# WG-DH-MB.net
KiCad netlist of a schematic drawn in Altium Designer
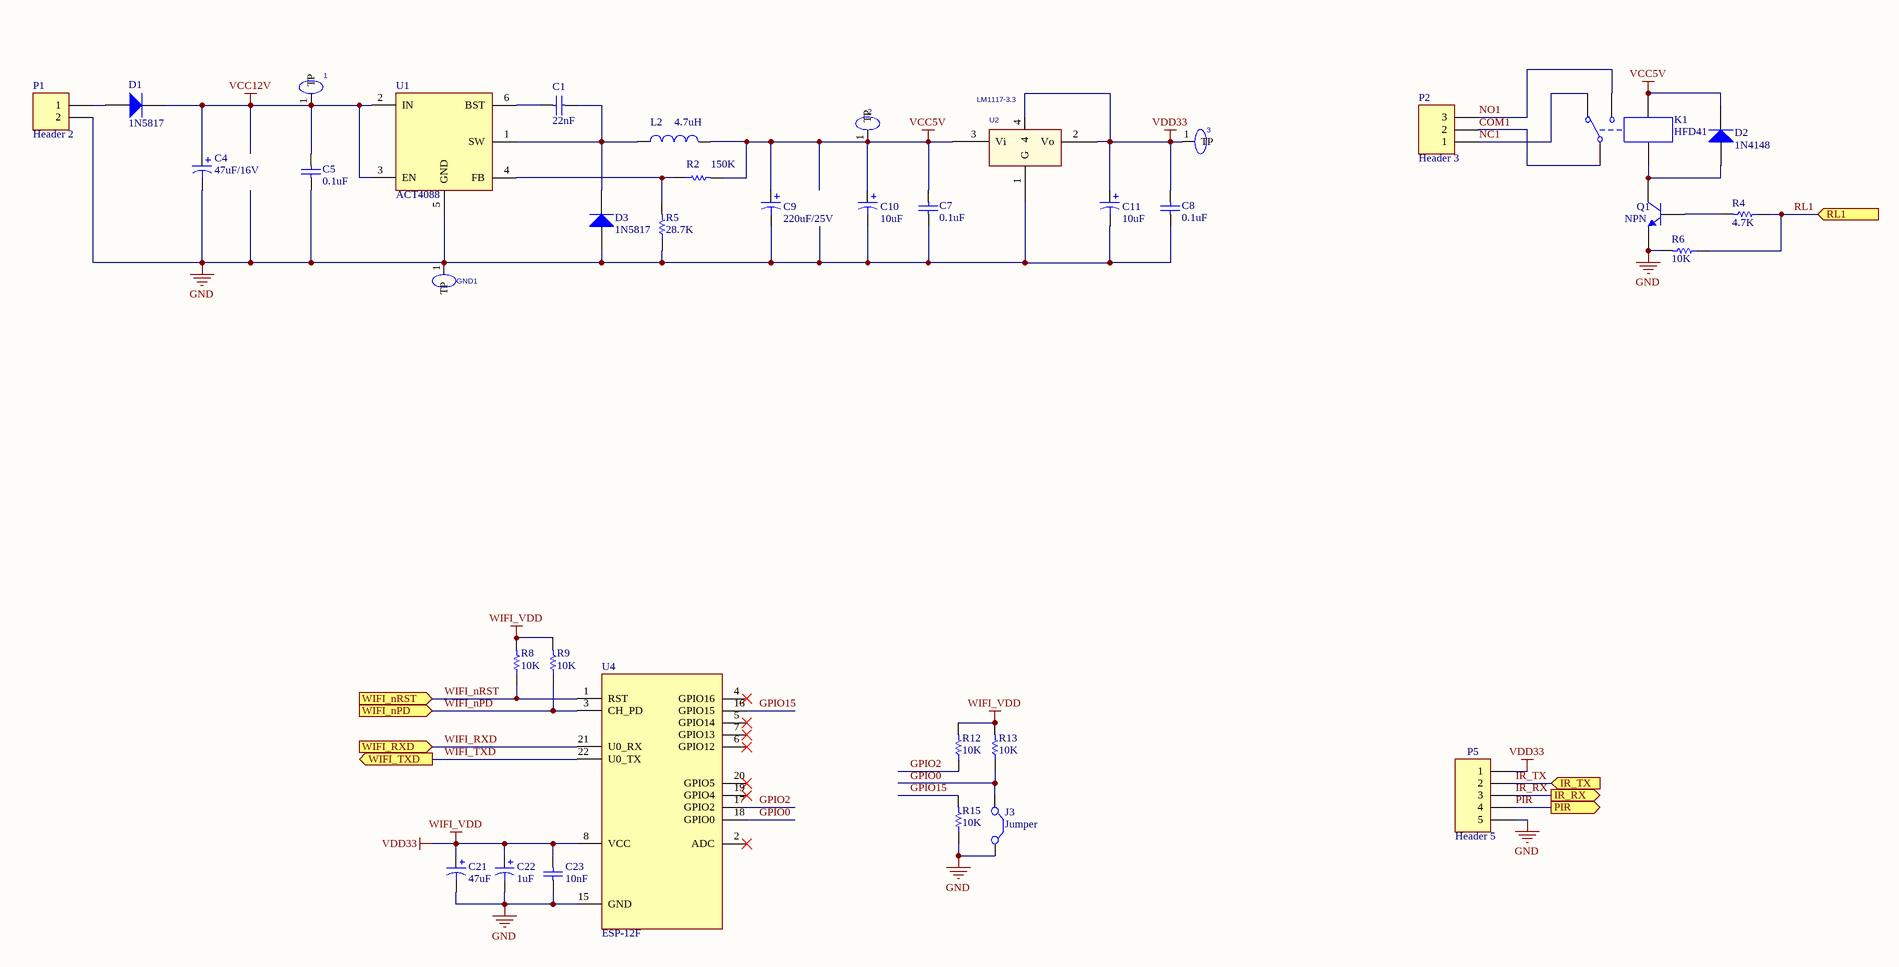
[diagram p0: WG-DH-MB.SchDoc, top left]
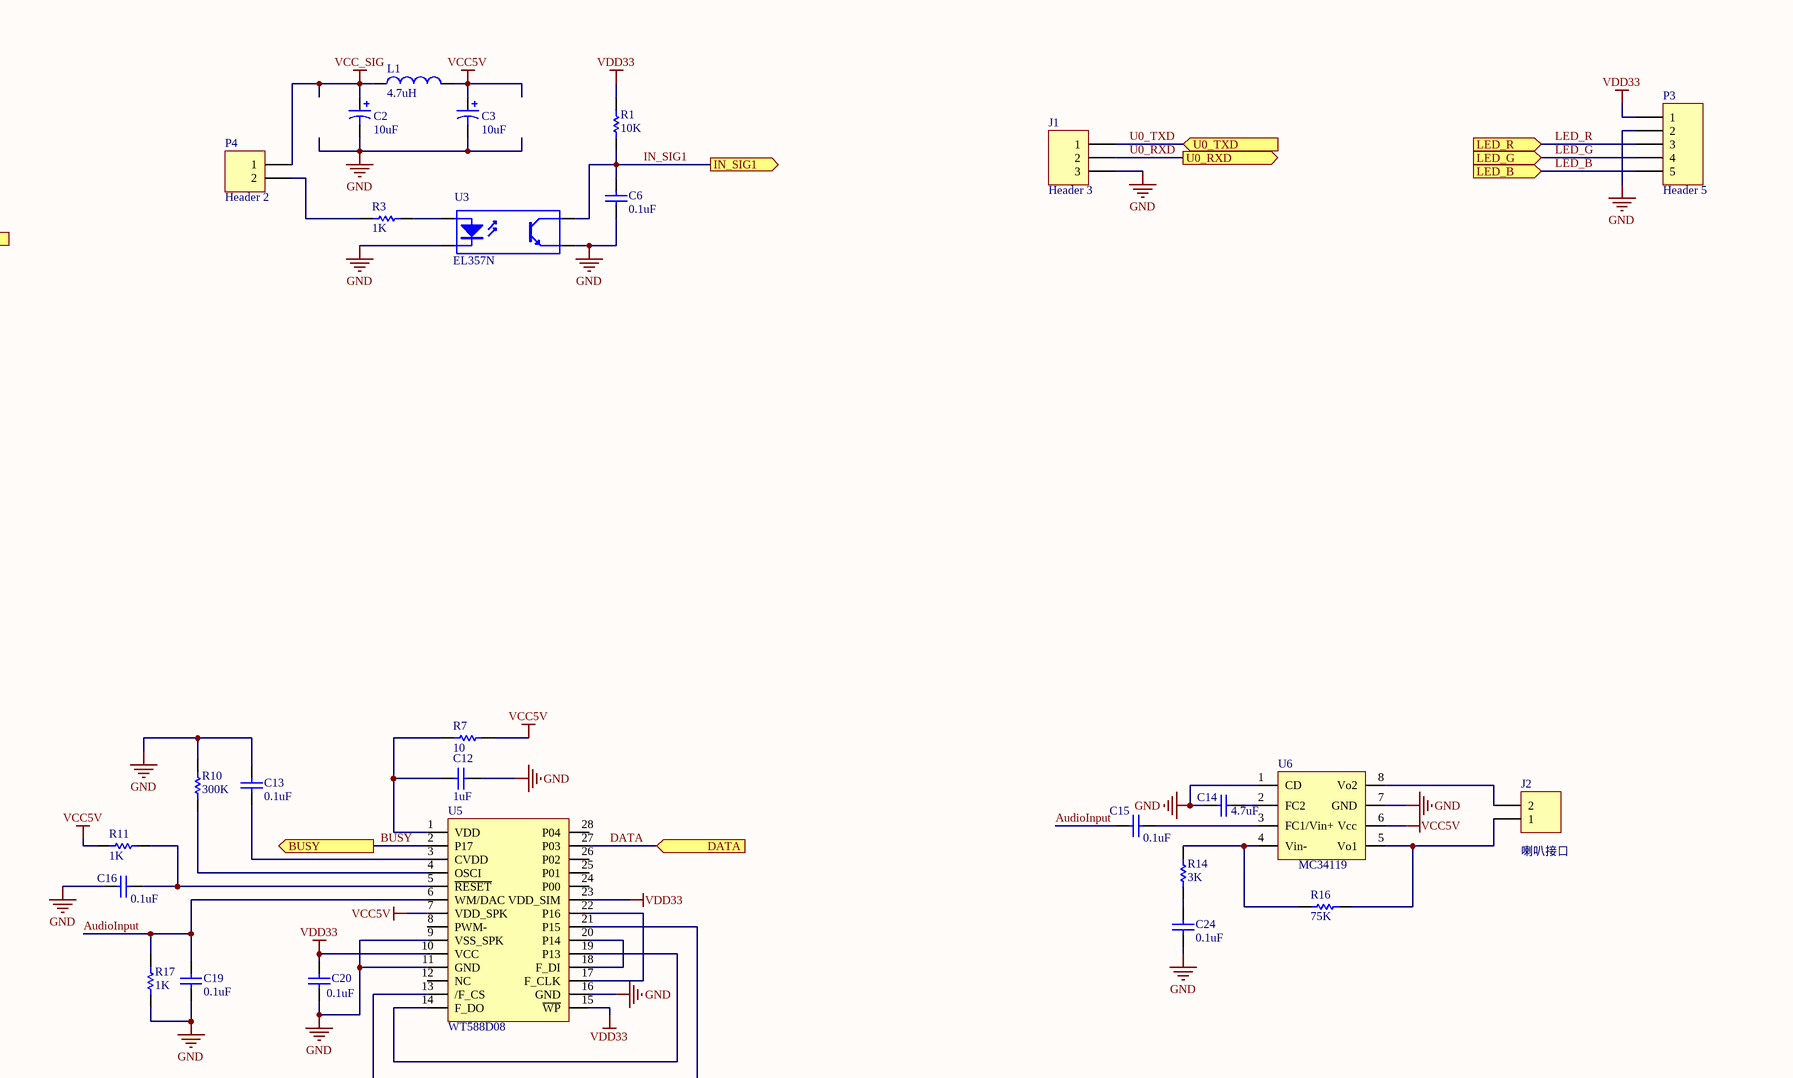
[diagram p1: WG-DH-MB.SchDoc, top right]
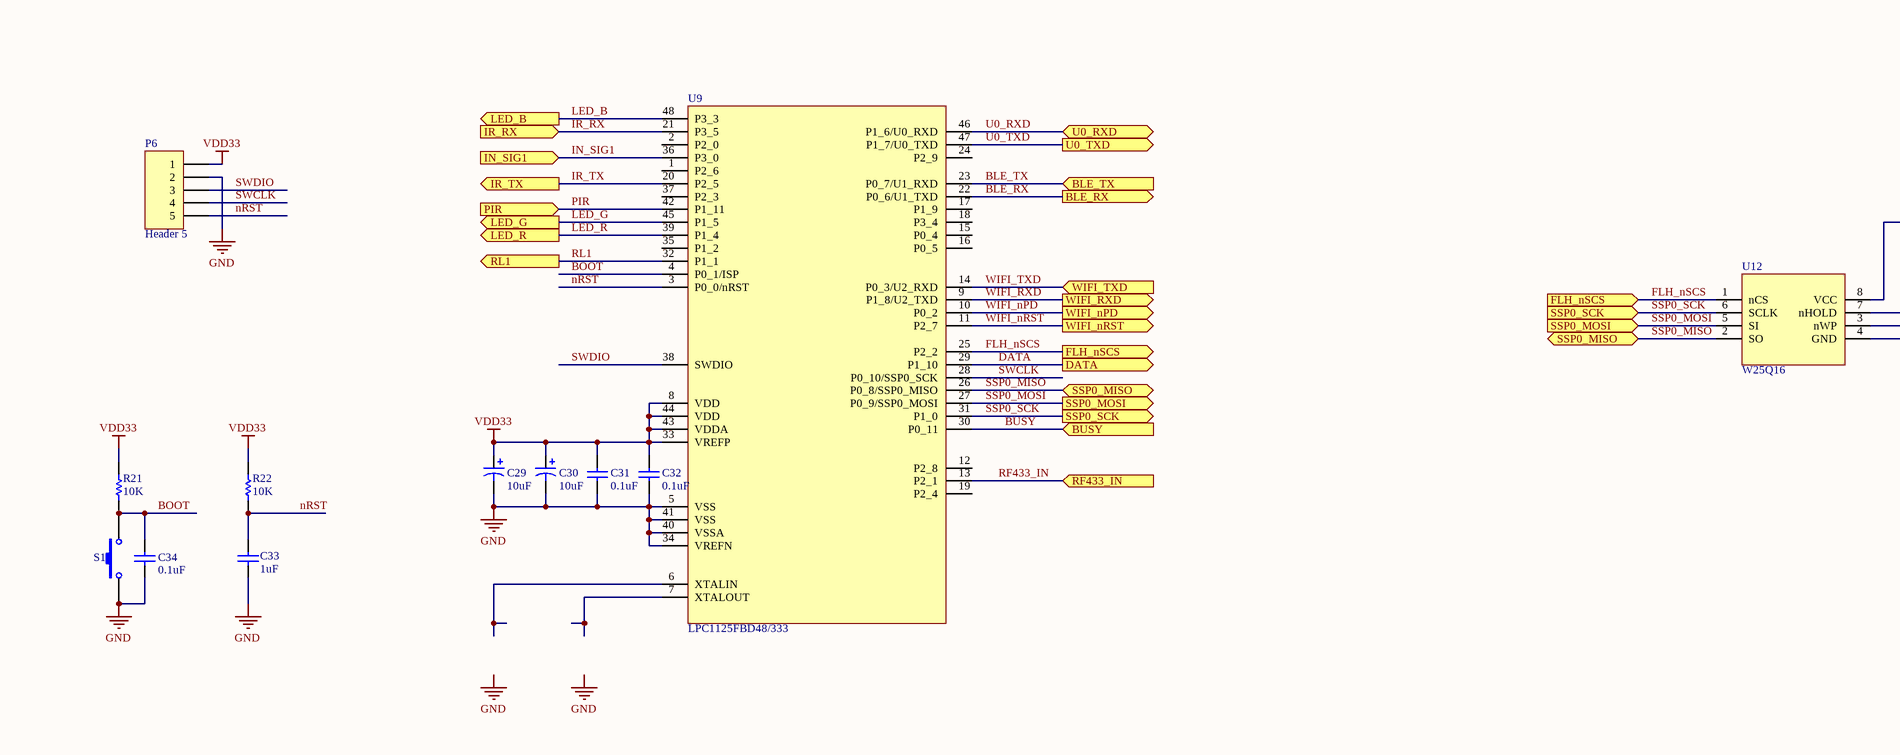
[diagram p2: WG-DH-MB.SchDoc, bottom left]
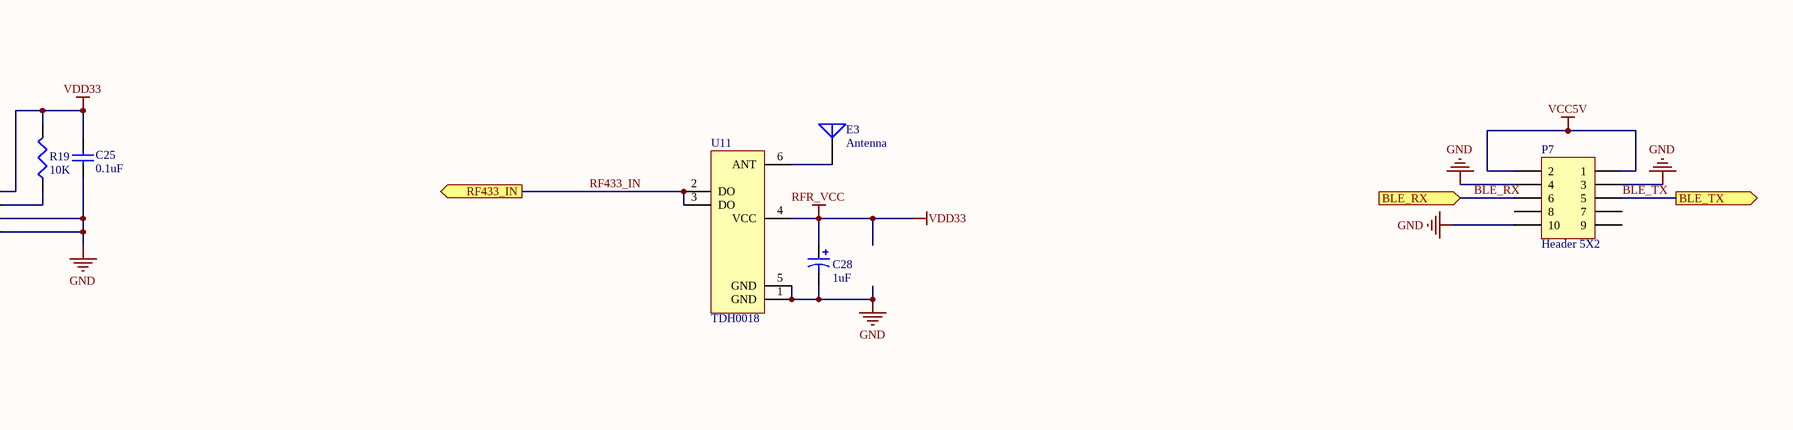
[diagram p3: WG-DH-MB.SchDoc, bottom right]

(export (version "E")
  (design (tool "Eeschema 10.0.6"))
  (components
    (comp (ref "1") (value "5VOUT") (libsource (lib "*") (part "TESTPOINT")))
    (comp (ref "2") (value "5VOUT") (libsource (lib "*") (part "TESTPOINT")))
    (comp (ref "3") (value "5VOUT") (libsource (lib "*") (part "TESTPOINT")))
    (comp (ref "C1")
      (value "22nF")
      (footprint "0805 - C")
      (description "Capacitor")
      (fields (field (name "PUBLISHER") "Altium Limited"))
      (libsource (lib "Miscellaneous Devices") (part "Cap"))
    )
    (comp (ref "C2")
      (value "10uF")
      (footprint "0805 - C")
      (description "Polarized Capacitor (Radial)")
      (fields (field (name "PUBLISHER") "Altium Limited"))
      (libsource (lib "Miscellaneous Devices") (part "Cap Pol1"))
    )
    (comp (ref "C3")
      (value "10uF")
      (footprint "0805 - C")
      (description "Polarized Capacitor (Radial)")
      (fields (field (name "PUBLISHER") "Altium Limited"))
      (libsource (lib "Miscellaneous Devices") (part "Cap Pol1"))
    )
    (comp (ref "C4")
      (value "47uF/16V")
      (footprint "smd_ec_d5.2")
      (description "Polarized Capacitor (Radial)")
      (fields (field (name "PUBLISHER") "Altium Limited"))
      (libsource (lib "Miscellaneous Devices") (part "Cap Pol1"))
    )
    (comp (ref "C5")
      (value "0.1uF")
      (footprint "0805 - C")
      (description "Capacitor")
      (fields (field (name "PUBLISHER") "Altium Limited"))
      (libsource (lib "Miscellaneous Devices") (part "Cap"))
    )
    (comp (ref "C6")
      (value "0.1uF")
      (footprint "0805 - C")
      (description "Capacitor")
      (fields (field (name "PUBLISHER") "Altium Limited"))
      (libsource (lib "Miscellaneous Devices") (part "Cap"))
    )
    (comp (ref "C7")
      (value "0.1uF")
      (footprint "0805 - C")
      (description "Capacitor")
      (fields (field (name "PUBLISHER") "Altium Limited"))
      (libsource (lib "Miscellaneous Devices") (part "Cap"))
    )
    (comp (ref "C8")
      (value "0.1uF")
      (footprint "0805 - C")
      (description "Capacitor")
      (fields (field (name "PUBLISHER") "Altium Limited"))
      (libsource (lib "Miscellaneous Devices") (part "Cap"))
    )
    (comp (ref "C9")
      (value "220uF/25V")
      (footprint "smd_ec_d8")
      (description "Polarized Capacitor (Radial)")
      (fields (field (name "PUBLISHER") "Altium Limited"))
      (libsource (lib "Miscellaneous Devices") (part "Cap Pol1"))
    )
    (comp (ref "C10")
      (value "10uF")
      (footprint "0805 - C")
      (description "Polarized Capacitor (Radial)")
      (fields (field (name "PUBLISHER") "Altium Limited"))
      (libsource (lib "Miscellaneous Devices") (part "Cap Pol1"))
    )
    (comp (ref "C11")
      (value "10uF")
      (footprint "0805 - C")
      (description "Polarized Capacitor (Radial)")
      (fields (field (name "PUBLISHER") "Altium Limited"))
      (libsource (lib "Miscellaneous Devices") (part "Cap Pol1"))
    )
    (comp (ref "C12")
      (value "1uF")
      (footprint "0805 - C")
      (description "Capacitor")
      (fields (field (name "PUBLISHER") "Altium Limited"))
      (libsource (lib "Miscellaneous Devices") (part "Cap"))
    )
    (comp (ref "C13")
      (value "0.1uF")
      (footprint "0805 - C")
      (description "Capacitor")
      (fields (field (name "PUBLISHER") "Altium Limited"))
      (libsource (lib "Miscellaneous Devices") (part "Cap"))
    )
    (comp (ref "C14")
      (value "4.7uF")
      (footprint "0805 - C")
      (description "Capacitor")
      (fields (field (name "PUBLISHER") "Altium Limited"))
      (libsource (lib "Miscellaneous Devices") (part "Cap"))
    )
    (comp (ref "C15")
      (value "0.1uF")
      (footprint "0805 - C")
      (description "Capacitor")
      (fields (field (name "PUBLISHER") "Altium Limited"))
      (libsource (lib "Miscellaneous Devices") (part "Cap"))
    )
    (comp (ref "C16")
      (value "0.1uF")
      (footprint "0805 - C")
      (description "Capacitor")
      (fields (field (name "PUBLISHER") "Altium Limited"))
      (libsource (lib "Miscellaneous Devices") (part "Cap"))
    )
    (comp (ref "C19")
      (value "0.1uF")
      (footprint "0805 - C")
      (description "Capacitor")
      (fields (field (name "PUBLISHER") "Altium Limited"))
      (libsource (lib "Miscellaneous Devices") (part "Cap"))
    )
    (comp (ref "C20")
      (value "0.1uF")
      (footprint "0805 - C")
      (description "Capacitor")
      (fields (field (name "PUBLISHER") "Altium Limited"))
      (libsource (lib "Miscellaneous Devices") (part "Cap"))
    )
    (comp (ref "C21")
      (value "47uF")
      (footprint "SMD_EC_D5.2")
      (description "Polarized Capacitor (Radial)")
      (fields (field (name "PUBLISHER") "Altium Limited"))
      (libsource (lib "Miscellaneous Devices") (part "Cap Pol1"))
    )
    (comp (ref "C22")
      (value "1uF")
      (footprint "0805 - C")
      (description "Polarized Capacitor (Radial)")
      (fields (field (name "PUBLISHER") "Altium Limited"))
      (libsource (lib "Miscellaneous Devices") (part "Cap Pol1"))
    )
    (comp (ref "C23")
      (value "10nF")
      (footprint "0805 - C")
      (description "Capacitor")
      (fields (field (name "PUBLISHER") "Altium Limited"))
      (libsource (lib "Miscellaneous Devices") (part "Cap"))
    )
    (comp (ref "C24")
      (value "0.1uF")
      (footprint "0805 - C")
      (description "Capacitor")
      (fields (field (name "PUBLISHER") "Altium Limited"))
      (libsource (lib "Miscellaneous Devices") (part "Cap"))
    )
    (comp (ref "C25")
      (value "0.1uF")
      (footprint "0805 - C")
      (description "Capacitor")
      (fields (field (name "PUBLISHER") "Altium Limited"))
      (libsource (lib "Miscellaneous Devices") (part "Cap"))
    )
    (comp (ref "C28")
      (value "1uF")
      (footprint "0805 - C")
      (description "Polarized Capacitor (Radial)")
      (fields (field (name "PUBLISHER") "Altium Limited"))
      (libsource (lib "Miscellaneous Devices") (part "Cap Pol1"))
    )
    (comp (ref "C29")
      (value "10uF")
      (footprint "0805 - C")
      (description "Polarized Capacitor (Radial)")
      (fields (field (name "PUBLISHER") "Altium Limited"))
      (libsource (lib "Miscellaneous Devices") (part "Cap Pol1"))
    )
    (comp (ref "C30")
      (value "10uF")
      (footprint "0805 - C")
      (description "Polarized Capacitor (Radial)")
      (fields (field (name "PUBLISHER") "Altium Limited"))
      (libsource (lib "Miscellaneous Devices") (part "Cap Pol1"))
    )
    (comp (ref "C31")
      (value "0.1uF")
      (footprint "0805 - C")
      (description "Capacitor")
      (fields (field (name "PUBLISHER") "Altium Limited"))
      (libsource (lib "Miscellaneous Devices") (part "Cap"))
    )
    (comp (ref "C32")
      (value "0.1uF")
      (footprint "0805 - C")
      (description "Capacitor")
      (fields (field (name "PUBLISHER") "Altium Limited"))
      (libsource (lib "Miscellaneous Devices") (part "Cap"))
    )
    (comp (ref "C33")
      (value "1uF")
      (footprint "0805 - C")
      (description "Capacitor")
      (fields (field (name "PUBLISHER") "Altium Limited"))
      (libsource (lib "Miscellaneous Devices") (part "Cap"))
    )
    (comp (ref "C34")
      (value "0.1uF")
      (footprint "0805 - C")
      (description "Capacitor")
      (fields (field (name "PUBLISHER") "Altium Limited"))
      (libsource (lib "Miscellaneous Devices") (part "Cap"))
    )
    (comp (ref "D1")
      (value "1N5817")
      (footprint "SMD_DIODE_SMA")
      (description "Default Diode")
      (fields (field (name "PUBLISHER") "Altium Limited"))
      (libsource (lib "Miscellaneous Devices") (part "Diode"))
    )
    (comp (ref "D2")
      (value "1N4148")
      (footprint "1n4148")
      (description "Default Diode")
      (fields (field (name "PUBLISHER") "Altium Limited"))
      (libsource (lib "Miscellaneous Devices") (part "Diode"))
    )
    (comp (ref "D3")
      (value "1N5817")
      (footprint "SMD_DIODE_SMA")
      (description "Default Diode")
      (fields (field (name "PUBLISHER") "Altium Limited"))
      (libsource (lib "Miscellaneous Devices") (part "Diode"))
    )
    (comp (ref "E3")
      (value "Antenna")
      (footprint "ant")
      (description "Generic Antenna")
      (fields (field (name "PUBLISHER") "Altium Limited"))
      (libsource (lib "Miscellaneous Devices") (part "Antenna"))
    )
    (comp (ref "GND1") (value "5VOUT") (libsource (lib "*") (part "TESTPOINT")))
    (comp (ref "J1")
      (value "Header 3")
      (footprint "HDR1X3")
      (description "Header, 3-Pin")
      (fields (field (name "PUBLISHER") "Altium Limited"))
      (libsource (lib "") (part "Header 3_1"))
    )
    (comp (ref "J2")
      (value "喇叭接口")
      (footprint "CN_1X2_P200")
      (description "Header, 2-Pin")
      (fields (field (name "PUBLISHER") "Altium Limited"))
      (libsource (lib "") (part "Header 2_1"))
    )
    (comp (ref "J3")
      (value "Jumper")
      (footprint "HDR1X2")
      (description "Jumper Wire")
      (fields (field (name "PUBLISHER") "Altium Limited"))
      (libsource (lib "Miscellaneous Devices") (part "Jumper"))
    )
    (comp (ref "K1")
      (value "HFD41")
      (footprint "HFD23")
      (description "Single-Pole Dual-Throw Relay")
      (fields (field (name "PUBLISHER") "Altium Limited"))
      (libsource (lib "Miscellaneous Devices") (part "Relay-SPDT"))
    )
    (comp (ref "L1")
      (value "4.7uH")
      (footprint "SMD_L_3015")
      (description "Inductor")
      (fields (field (name "PUBLISHER") "Altium Limited"))
      (libsource (lib "Miscellaneous Devices") (part "Inductor"))
    )
    (comp (ref "L2")
      (value "4.7uH")
      (footprint "SMD_L_3015")
      (description "Inductor")
      (fields (field (name "PUBLISHER") "Altium Limited"))
      (libsource (lib "Miscellaneous Devices") (part "Inductor"))
    )
    (comp (ref "P1")
      (value "Header 2")
      (footprint "CON2-5.08")
      (description "Header, 2-Pin")
      (fields (field (name "PUBLISHER") "Altium Limited"))
      (libsource (lib "Miscellaneous Connectors") (part "Header 2"))
    )
    (comp (ref "P2")
      (value "Header 3")
      (footprint "CN_1X3_P200")
      (description "Header, 3-Pin")
      (fields (field (name "PUBLISHER") "Altium Limited"))
      (libsource (lib "Miscellaneous Connectors") (part "Header 3"))
    )
    (comp (ref "P3")
      (value "Header 5")
      (footprint "CN_1X5_P200")
      (description "Header, 5-Pin")
      (fields (field (name "PUBLISHER") "Altium Limited"))
      (libsource (lib "Miscellaneous Connectors") (part "Header 5"))
    )
    (comp (ref "P4")
      (value "Header 2")
      (footprint "CN_1X2_P200")
      (description "Header, 2-Pin")
      (fields (field (name "PUBLISHER") "Altium Limited"))
      (libsource (lib "Miscellaneous Connectors") (part "Header 2"))
    )
    (comp (ref "P5")
      (value "Header 5")
      (footprint "HDR1X5")
      (description "Header, 5-Pin")
      (fields (field (name "PUBLISHER") "Altium Limited"))
      (libsource (lib "") (part "Header 5_1"))
    )
    (comp (ref "P6")
      (value "Header 5")
      (footprint "CN_1X5_P200")
      (description "Header, 5-Pin")
      (fields (field (name "PUBLISHER") "Altium Limited"))
      (libsource (lib "") (part "Header 5_1"))
    )
    (comp (ref "P7")
      (value "Header 5X2")
      (footprint "HDR2X5")
      (description "Header, 5-Pin, Dual row")
      (fields (field (name "PUBLISHER") "Altium Limited"))
      (libsource (lib "Miscellaneous Connectors") (part "Header 5X2"))
    )
    (comp (ref "Q1")
      (value "NPN")
      (footprint "SOT23")
      (description "NPN Bipolar Transistor")
      (fields (field (name "PUBLISHER") "Altium Limited"))
      (libsource (lib "Miscellaneous Devices") (part "NPN"))
    )
    (comp (ref "R1")
      (value "10K")
      (footprint "0805 - R")
      (description "Resistor")
      (fields (field (name "PUBLISHER") "Altium Limited"))
      (libsource (lib "Miscellaneous Devices") (part "Res1"))
    )
    (comp (ref "R2")
      (value "150K")
      (footprint "0805 - R")
      (description "Resistor")
      (fields (field (name "PUBLISHER") "Altium Limited"))
      (libsource (lib "Miscellaneous Devices") (part "Res1"))
    )
    (comp (ref "R3")
      (value "1K")
      (footprint "0805 - R")
      (description "Resistor")
      (fields (field (name "PUBLISHER") "Altium Limited"))
      (libsource (lib "Miscellaneous Devices") (part "Res1"))
    )
    (comp (ref "R4")
      (value "4.7K")
      (footprint "0805 - R")
      (description "Resistor")
      (fields (field (name "PUBLISHER") "Altium Limited"))
      (libsource (lib "Miscellaneous Devices") (part "Res1"))
    )
    (comp (ref "R5")
      (value "28.7K")
      (footprint "0805 - R")
      (description "Resistor")
      (fields (field (name "PUBLISHER") "Altium Limited"))
      (libsource (lib "Miscellaneous Devices") (part "Res1"))
    )
    (comp (ref "R6")
      (value "10K")
      (footprint "0805 - R")
      (description "Resistor")
      (fields (field (name "PUBLISHER") "Altium Limited"))
      (libsource (lib "Miscellaneous Devices") (part "Res1"))
    )
    (comp (ref "R7")
      (value "10")
      (footprint "0805 - R")
      (description "Resistor")
      (fields (field (name "PUBLISHER") "Altium Limited"))
      (libsource (lib "Miscellaneous Devices") (part "Res1"))
    )
    (comp (ref "R8")
      (value "10K")
      (footprint "0805 - R")
      (description "Resistor")
      (fields (field (name "PUBLISHER") "Altium Limited"))
      (libsource (lib "Miscellaneous Devices") (part "Res1"))
    )
    (comp (ref "R9")
      (value "10K")
      (footprint "0805 - R")
      (description "Resistor")
      (fields (field (name "PUBLISHER") "Altium Limited"))
      (libsource (lib "Miscellaneous Devices") (part "Res1"))
    )
    (comp (ref "R10")
      (value "300K")
      (footprint "0805 - R")
      (description "Resistor")
      (fields (field (name "PUBLISHER") "Altium Limited"))
      (libsource (lib "Miscellaneous Devices") (part "Res1"))
    )
    (comp (ref "R11")
      (value "1K")
      (footprint "0805 - R")
      (description "Resistor")
      (fields (field (name "PUBLISHER") "Altium Limited"))
      (libsource (lib "Miscellaneous Devices") (part "Res1"))
    )
    (comp (ref "R12")
      (value "10K")
      (footprint "0805 - R")
      (description "Resistor")
      (fields (field (name "PUBLISHER") "Altium Limited"))
      (libsource (lib "Miscellaneous Devices") (part "Res1"))
    )
    (comp (ref "R13")
      (value "10K")
      (footprint "0805 - R")
      (description "Resistor")
      (fields (field (name "PUBLISHER") "Altium Limited"))
      (libsource (lib "Miscellaneous Devices") (part "Res1"))
    )
    (comp (ref "R14")
      (value "3K")
      (footprint "0805 - R")
      (description "Resistor")
      (fields (field (name "PUBLISHER") "Altium Limited"))
      (libsource (lib "Miscellaneous Devices") (part "Res1"))
    )
    (comp (ref "R15")
      (value "10K")
      (footprint "0805 - R")
      (description "Resistor")
      (fields (field (name "PUBLISHER") "Altium Limited"))
      (libsource (lib "Miscellaneous Devices") (part "Res1"))
    )
    (comp (ref "R16")
      (value "75K")
      (footprint "0805 - R")
      (description "Resistor")
      (fields (field (name "PUBLISHER") "Altium Limited"))
      (libsource (lib "Miscellaneous Devices") (part "Res1"))
    )
    (comp (ref "R17")
      (value "1K")
      (footprint "0805 - R")
      (description "Resistor")
      (fields (field (name "PUBLISHER") "Altium Limited"))
      (libsource (lib "Miscellaneous Devices") (part "Res1"))
    )
    (comp (ref "R19")
      (value "10K")
      (footprint "0805 - R")
      (description "Resistor")
      (fields (field (name "PUBLISHER") "Altium Limited"))
      (libsource (lib "Miscellaneous Devices") (part "Res3"))
    )
    (comp (ref "R21")
      (value "10K")
      (footprint "0805 - R")
      (description "Resistor")
      (fields (field (name "PUBLISHER") "Altium Limited"))
      (libsource (lib "Miscellaneous Devices") (part "Res1"))
    )
    (comp (ref "R22")
      (value "10K")
      (footprint "0805 - R")
      (description "Resistor")
      (fields (field (name "PUBLISHER") "Altium Limited"))
      (libsource (lib "Miscellaneous Devices") (part "Res1"))
    )
    (comp (ref "S1")
      (value "SW-PB")
      (footprint "SW_SMD_2P")
      (description "Switch")
      (fields (field (name "PUBLISHER") "Altium Limited"))
      (libsource (lib "Miscellaneous Devices") (part "SW-PB"))
    )
    (comp (ref "U1") (value "ACT4088") (footprint "SOT23-6") (libsource (lib "Gsd") (part "ACT4088")))
    (comp (ref "U2") (value "LM1117-3.3") (libsource (lib "*") (part "LM1117_1")))
    (comp (ref "U3")
      (value "EL357N")
      (footprint "SOP4")
      (description "4-Pin Phototransistor Optocoupler")
      (fields (field (name "PUBLISHER") "Altium Limited"))
      (libsource (lib "Miscellaneous Devices") (part "Optoisolator1"))
    )
    (comp (ref "U4") (value "ESP-12F") (footprint "WIFI-ESP") (libsource (lib "Gsd") (part "ESP-12F")))
    (comp (ref "U5") (value "WT588D08") (footprint "WT588D08") (libsource (lib "GW-FP") (part "WT588D08")))
    (comp (ref "U6") (value "MC34119") (footprint "MC34119") (libsource (lib "GW-FP") (part "MC34119")))
    (comp (ref "U9")
      (value "LPC1125FBD48/333")
      (footprint "TQFP48")
      (libsource (lib "Gsd") (part "LPC1125FBD48/333"))
    )
    (comp (ref "U11") (value "TDH0018") (footprint "TDH0018") (libsource (lib "Gsd") (part "TDH0018")))
    (comp (ref "U12") (value "W25Q16") (footprint "CN_4X2P_1.27MM") (libsource (lib "Gsd") (part "MX25Lxx")))
  )
  (nets
    (net (code "1") (name "/AudioInput") (class "Default")
      (node (ref "C15") (pin "1") (pinfunction "1_1") (pintype "passive"))
      (node (ref "C19") (pin "1") (pinfunction "1_1") (pintype "passive"))
      (node (ref "R17") (pin "2") (pinfunction "2_2") (pintype "passive"))
      (node (ref "U5") (pin "6") (pinfunction "WM/DAC_6") (pintype "passive"))
    )
    (net (code "2") (name "/BLE_RX") (class "Default")
      (node (ref "P7") (pin "6") (pinfunction "6_6") (pintype "passive"))
      (node (ref "U9") (pin "22") (pinfunction "P0_6/U1_TXD_22") (pintype "passive"))
    )
    (net (code "3") (name "/BLE_TX") (class "Default")
      (node (ref "P7") (pin "5") (pinfunction "5_5") (pintype "passive"))
      (node (ref "U9") (pin "23") (pinfunction "P0_7/U1_RXD_23") (pintype "passive"))
    )
    (net (code "4") (name "/BOOT") (class "Default")
      (node (ref "C34") (pin "2") (pinfunction "2_2") (pintype "passive"))
      (node (ref "R21") (pin "2") (pinfunction "2_2") (pintype "passive"))
      (node (ref "S1") (pin "2") (pinfunction "2_2") (pintype "passive"))
      (node (ref "U9") (pin "4") (pinfunction "P0_1/ISP_4") (pintype "passive"))
    )
    (net (code "5") (name "/BUSY") (class "Default")
      (node (ref "U5") (pin "2") (pinfunction "P17_2") (pintype "passive"))
      (node (ref "U9") (pin "30") (pinfunction "P0_11_30") (pintype "passive"))
    )
    (net (code "6") (name "/COM1") (class "Default")
      (node (ref "K1") (pin "1") (pinfunction "1_1") (pintype "passive"))
      (node (ref "P2") (pin "2") (pinfunction "2_2") (pintype "passive"))
    )
    (net (code "7") (name "/DATA") (class "Default")
      (node (ref "U5") (pin "27") (pinfunction "P03_27") (pintype "passive"))
      (node (ref "U9") (pin "29") (pinfunction "P1_10_29") (pintype "passive"))
    )
    (net (code "8") (name "/FLH_nSCS") (class "Default")
      (node (ref "U12") (pin "1") (pinfunction "nCS_1") (pintype "passive"))
      (node (ref "U9") (pin "25") (pinfunction "P2_2_25") (pintype "passive"))
    )
    (net (code "9") (name "/GPIO0") (class "Default")
      (node (ref "J3") (pin "1") (pinfunction "C1_1") (pintype "passive"))
      (node (ref "R13") (pin "1") (pinfunction "1_1") (pintype "passive"))
      (node (ref "U4") (pin "18") (pinfunction "GPIO0_18") (pintype "passive"))
    )
    (net (code "10") (name "/GPIO2") (class "Default")
      (node (ref "R12") (pin "1") (pinfunction "1_1") (pintype "passive"))
      (node (ref "U4") (pin "17") (pinfunction "GPIO2_17") (pintype "passive"))
    )
    (net (code "11") (name "/GPIO15") (class "Default")
      (node (ref "R15") (pin "2") (pinfunction "2_2") (pintype "passive"))
      (node (ref "U4") (pin "16") (pinfunction "GPIO15_16") (pintype "passive"))
    )
    (net (code "12") (name "/IN_SIG1") (class "Default")
      (node (ref "C6") (pin "2") (pinfunction "2_2") (pintype "passive"))
      (node (ref "R1") (pin "2") (pinfunction "2_2") (pintype "passive"))
      (node (ref "U3") (pin "4") (pinfunction "C_4") (pintype "passive"))
      (node (ref "U9") (pin "36") (pinfunction "P3_0_36") (pintype "passive"))
    )
    (net (code "13") (name "/IR_RX") (class "Default")
      (node (ref "P5") (pin "3") (pinfunction "3_3") (pintype "passive"))
      (node (ref "U9") (pin "21") (pinfunction "P3_5_21") (pintype "passive"))
    )
    (net (code "14") (name "/IR_TX") (class "Default")
      (node (ref "P5") (pin "2") (pinfunction "2_2") (pintype "passive"))
      (node (ref "U9") (pin "20") (pinfunction "P2_5_20") (pintype "passive"))
    )
    (net (code "15") (name "/LED_B") (class "Default")
      (node (ref "P3") (pin "5") (pinfunction "5_5") (pintype "passive"))
      (node (ref "U9") (pin "48") (pinfunction "P3_3_48") (pintype "passive"))
    )
    (net (code "16") (name "/LED_G") (class "Default")
      (node (ref "P3") (pin "4") (pinfunction "4_4") (pintype "passive"))
      (node (ref "U9") (pin "45") (pinfunction "P1_5_45") (pintype "passive"))
    )
    (net (code "17") (name "/LED_R") (class "Default")
      (node (ref "P3") (pin "3") (pinfunction "3_3") (pintype "passive"))
      (node (ref "U9") (pin "39") (pinfunction "P1_4_39") (pintype "passive"))
    )
    (net (code "18") (name "/NC1") (class "Default")
      (node (ref "K1") (pin "2") (pinfunction "2_2") (pintype "passive"))
      (node (ref "P2") (pin "1") (pinfunction "1_1") (pintype "passive"))
    )
    (net (code "19") (name "/NO1") (class "Default")
      (node (ref "K1") (pin "3") (pinfunction "3_3") (pintype "passive"))
      (node (ref "P2") (pin "3") (pinfunction "3_3") (pintype "passive"))
    )
    (net (code "20") (name "/PIR") (class "Default")
      (node (ref "P5") (pin "4") (pinfunction "4_4") (pintype "passive"))
      (node (ref "U9") (pin "42") (pinfunction "P1_11_42") (pintype "passive"))
    )
    (net (code "21") (name "/RF433_IN") (class "Default")
      (node (ref "U11") (pin "2") (pinfunction "DO_2") (pintype "passive"))
      (node (ref "U11") (pin "3") (pinfunction "DO_3") (pintype "passive"))
      (node (ref "U9") (pin "13") (pinfunction "P2_1_13") (pintype "passive"))
    )
    (net (code "22") (name "/RL1") (class "Default")
      (node (ref "R4") (pin "1") (pinfunction "1_1") (pintype "passive"))
      (node (ref "R6") (pin "1") (pinfunction "1_1") (pintype "passive"))
      (node (ref "U9") (pin "32") (pinfunction "P1_1_32") (pintype "passive"))
    )
    (net (code "23") (name "/SSP0_MISO") (class "Default")
      (node (ref "U12") (pin "2") (pinfunction "SO_2") (pintype "passive"))
      (node (ref "U9") (pin "26") (pinfunction "P0_8/SSP0_MISO_26") (pintype "passive"))
    )
    (net (code "24") (name "/SSP0_MOSI") (class "Default")
      (node (ref "U12") (pin "5") (pinfunction "SI_5") (pintype "passive"))
      (node (ref "U9") (pin "27") (pinfunction "P0_9/SSP0_MOSI_27") (pintype "passive"))
    )
    (net (code "25") (name "/SSP0_SCK") (class "Default")
      (node (ref "U12") (pin "6") (pinfunction "SCLK_6") (pintype "passive"))
      (node (ref "U9") (pin "31") (pinfunction "P1_0_31") (pintype "passive"))
    )
    (net (code "26") (name "/SWCLK") (class "Default")
      (node (ref "P6") (pin "4") (pinfunction "4_4") (pintype "passive"))
      (node (ref "U9") (pin "28") (pinfunction "P0_10/SSP0_SCK_28") (pintype "passive"))
    )
    (net (code "27") (name "/SWDIO") (class "Default")
      (node (ref "P6") (pin "3") (pinfunction "3_3") (pintype "passive"))
      (node (ref "U9") (pin "38") (pinfunction "SWDIO_38") (pintype "passive"))
    )
    (net (code "28") (name "/U0_RXD") (class "Default")
      (node (ref "J1") (pin "2") (pinfunction "2_2") (pintype "passive"))
      (node (ref "U9") (pin "46") (pinfunction "P1_6/U0_RXD_46") (pintype "passive"))
    )
    (net (code "29") (name "/U0_TXD") (class "Default")
      (node (ref "J1") (pin "1") (pinfunction "1_1") (pintype "passive"))
      (node (ref "U9") (pin "47") (pinfunction "P1_7/U0_TXD_47") (pintype "passive"))
    )
    (net (code "30") (name "/WIFI_RXD") (class "Default")
      (node (ref "U4") (pin "21") (pinfunction "U0_RX_21") (pintype "passive"))
      (node (ref "U9") (pin "9") (pinfunction "P1_8/U2_TXD_9") (pintype "passive"))
    )
    (net (code "31") (name "/WIFI_TXD") (class "Default")
      (node (ref "U4") (pin "22") (pinfunction "U0_TX_22") (pintype "passive"))
      (node (ref "U9") (pin "14") (pinfunction "P0_3/U2_RXD_14") (pintype "passive"))
    )
    (net (code "32") (name "/WIFI_nPD") (class "Default")
      (node (ref "R9") (pin "1") (pinfunction "1_1") (pintype "passive"))
      (node (ref "U4") (pin "3") (pinfunction "CH_PD_3") (pintype "passive"))
      (node (ref "U9") (pin "10") (pinfunction "P0_2_10") (pintype "passive"))
    )
    (net (code "33") (name "/WIFI_nRST") (class "Default")
      (node (ref "R8") (pin "1") (pinfunction "1_1") (pintype "passive"))
      (node (ref "U4") (pin "1") (pinfunction "RST_1") (pintype "passive"))
      (node (ref "U9") (pin "11") (pinfunction "P2_7_11") (pintype "passive"))
    )
    (net (code "34") (name "/nRST") (class "Default")
      (node (ref "C33") (pin "2") (pinfunction "2_2") (pintype "passive"))
      (node (ref "P6") (pin "5") (pinfunction "5_5") (pintype "passive"))
      (node (ref "R22") (pin "2") (pinfunction "2_2") (pintype "passive"))
      (node (ref "U9") (pin "3") (pinfunction "P0_0/nRST_3") (pintype "passive"))
    )
    (net (code "35") (name "GND") (class "Default")
      (node (ref "C10") (pin "2") (pinfunction "2_2") (pintype "passive"))
      (node (ref "C11") (pin "2") (pinfunction "2_2") (pintype "passive"))
      (node (ref "C12") (pin "1") (pinfunction "1_1") (pintype "passive"))
      (node (ref "C13") (pin "1") (pinfunction "1_1") (pintype "passive"))
      (node (ref "C14") (pin "2") (pinfunction "2_2") (pintype "passive"))
      (node (ref "C16") (pin "1") (pinfunction "1_1") (pintype "passive"))
      (node (ref "C19") (pin "2") (pinfunction "2_2") (pintype "passive"))
      (node (ref "C2") (pin "2") (pinfunction "2_2") (pintype "passive"))
      (node (ref "C20") (pin "2") (pinfunction "2_2") (pintype "passive"))
      (node (ref "C21") (pin "2") (pinfunction "2_2") (pintype "passive"))
      (node (ref "C22") (pin "2") (pinfunction "2_2") (pintype "passive"))
      (node (ref "C23") (pin "1") (pinfunction "1_1") (pintype "passive"))
      (node (ref "C24") (pin "1") (pinfunction "1_1") (pintype "passive"))
      (node (ref "C25") (pin "1") (pinfunction "1_1") (pintype "passive"))
      (node (ref "C28") (pin "2") (pinfunction "2_2") (pintype "passive"))
      (node (ref "C29") (pin "2") (pinfunction "2_2") (pintype "passive"))
      (node (ref "C3") (pin "2") (pinfunction "2_2") (pintype "passive"))
      (node (ref "C30") (pin "2") (pinfunction "2_2") (pintype "passive"))
      (node (ref "C31") (pin "1") (pinfunction "1_1") (pintype "passive"))
      (node (ref "C32") (pin "1") (pinfunction "1_1") (pintype "passive"))
      (node (ref "C33") (pin "1") (pinfunction "1_1") (pintype "passive"))
      (node (ref "C34") (pin "1") (pinfunction "1_1") (pintype "passive"))
      (node (ref "C4") (pin "2") (pinfunction "2_2") (pintype "passive"))
      (node (ref "C5") (pin "1") (pinfunction "1_1") (pintype "passive"))
      (node (ref "C6") (pin "1") (pinfunction "1_1") (pintype "passive"))
      (node (ref "C7") (pin "1") (pinfunction "1_1") (pintype "passive"))
      (node (ref "C8") (pin "1") (pinfunction "1_1") (pintype "passive"))
      (node (ref "C9") (pin "2") (pinfunction "2_2") (pintype "passive"))
      (node (ref "D3") (pin "1") (pinfunction "A_1") (pintype "passive"))
      (node (ref "GND1") (pin "1") (pinfunction "TP_1") (pintype "passive"))
      (node (ref "J1") (pin "3") (pinfunction "3_3") (pintype "passive"))
      (node (ref "J3") (pin "2") (pinfunction "C2_2") (pintype "passive"))
      (node (ref "P1") (pin "2") (pinfunction "2_2") (pintype "passive"))
      (node (ref "P3") (pin "2") (pinfunction "2_2") (pintype "passive"))
      (node (ref "P5") (pin "5") (pinfunction "5_5") (pintype "passive"))
      (node (ref "P6") (pin "2") (pinfunction "2_2") (pintype "passive"))
      (node (ref "P7") (pin "10") (pinfunction "10_10") (pintype "passive"))
      (node (ref "P7") (pin "3") (pinfunction "3_3") (pintype "passive"))
      (node (ref "P7") (pin "4") (pinfunction "4_4") (pintype "passive"))
      (node (ref "Q1") (pin "3") (pinfunction "E_3") (pintype "passive"))
      (node (ref "R10") (pin "2") (pinfunction "2_2") (pintype "passive"))
      (node (ref "R15") (pin "1") (pinfunction "1_1") (pintype "passive"))
      (node (ref "R17") (pin "1") (pinfunction "1_1") (pintype "passive"))
      (node (ref "R5") (pin "1") (pinfunction "1_1") (pintype "passive"))
      (node (ref "R6") (pin "2") (pinfunction "2_2") (pintype "passive"))
      (node (ref "S1") (pin "1") (pinfunction "1_1") (pintype "passive"))
      (node (ref "U1") (pin "5") (pinfunction "GND_5") (pintype "passive"))
      (node (ref "U11") (pin "1") (pinfunction "GND_1") (pintype "passive"))
      (node (ref "U11") (pin "5") (pinfunction "GND_5") (pintype "passive"))
      (node (ref "U12") (pin "3") (pinfunction "nWP_3") (pintype "passive"))
      (node (ref "U12") (pin "4") (pinfunction "GND_4") (pintype "passive"))
      (node (ref "U2") (pin "1") (pinfunction "G_1") (pintype "passive"))
      (node (ref "U3") (pin "2") (pinfunction "K_2") (pintype "passive"))
      (node (ref "U3") (pin "3") (pinfunction "E_3") (pintype "passive"))
      (node (ref "U4") (pin "15") (pinfunction "GND_15") (pintype "passive"))
      (node (ref "U5") (pin "11") (pinfunction "GND_11") (pintype "passive"))
      (node (ref "U5") (pin "16") (pinfunction "GND_16") (pintype "passive"))
      (node (ref "U5") (pin "9") (pinfunction "VSS_SPK_9") (pintype "passive"))
      (node (ref "U6") (pin "1") (pinfunction "CD_1") (pintype "passive"))
      (node (ref "U6") (pin "7") (pinfunction "GND_7") (pintype "passive"))
      (node (ref "U9") (pin "34") (pinfunction "VREFN_34") (pintype "passive"))
      (node (ref "U9") (pin "40") (pinfunction "VSSA_40") (pintype "passive"))
      (node (ref "U9") (pin "41") (pinfunction "VSS_41") (pintype "passive"))
      (node (ref "U9") (pin "5") (pinfunction "VSS_5") (pintype "passive"))
    )
    (net (code "36") (name "Net-(C24-Pad2)") (class "Default")
      (node (ref "C24") (pin "2") (pinfunction "2_2") (pintype "passive"))
      (node (ref "R14") (pin "1") (pinfunction "1_1") (pintype "passive"))
    )
    (net (code "37") (name "Net-(D1-A)") (class "Default")
      (node (ref "D1") (pin "1") (pinfunction "A_1") (pintype "passive"))
      (node (ref "P1") (pin "1") (pinfunction "1_1") (pintype "passive"))
    )
    (net (code "38") (name "Net-(D2-A)") (class "Default")
      (node (ref "D2") (pin "1") (pinfunction "A_1") (pintype "passive"))
      (node (ref "K1") (pin "4") (pinfunction "4_4") (pintype "passive"))
      (node (ref "Q1") (pin "1") (pinfunction "C_1") (pintype "passive"))
    )
    (net (code "39") (name "Net-(D3-K)") (class "Default")
      (node (ref "C1") (pin "1") (pinfunction "1_1") (pintype "passive"))
      (node (ref "D3") (pin "2") (pinfunction "K_2") (pintype "passive"))
      (node (ref "L2") (pin "1") (pinfunction "1_1") (pintype "passive"))
      (node (ref "U1") (pin "1") (pinfunction "SW_1") (pintype "passive"))
    )
    (net (code "40") (name "Net-(E3-A)") (class "Default")
      (node (ref "E3") (pin "1") (pinfunction "A_1") (pintype "passive"))
      (node (ref "U11") (pin "6") (pinfunction "ANT_6") (pintype "passive"))
    )
    (net (code "41") (name "Net-(P4-Pad2)") (class "Default")
      (node (ref "P4") (pin "2") (pinfunction "2_2") (pintype "passive"))
      (node (ref "R3") (pin "2") (pinfunction "2_2") (pintype "passive"))
    )
    (net (code "42") (name "Net-(Q1-B)") (class "Default")
      (node (ref "Q1") (pin "2") (pinfunction "B_2") (pintype "passive"))
      (node (ref "R4") (pin "2") (pinfunction "2_2") (pintype "passive"))
    )
    (net (code "43") (name "Net-(U1-BST)") (class "Default")
      (node (ref "C1") (pin "2") (pinfunction "2_2") (pintype "passive"))
      (node (ref "U1") (pin "6") (pinfunction "BST_6") (pintype "passive"))
    )
    (net (code "44") (name "Net-(U1-FB)") (class "Default")
      (node (ref "R2") (pin "1") (pinfunction "1_1") (pintype "passive"))
      (node (ref "R5") (pin "2") (pinfunction "2_2") (pintype "passive"))
      (node (ref "U1") (pin "4") (pinfunction "FB_4") (pintype "passive"))
    )
    (net (code "45") (name "Net-(U3-A)") (class "Default")
      (node (ref "R3") (pin "1") (pinfunction "1_1") (pintype "passive"))
      (node (ref "U3") (pin "1") (pinfunction "A_1") (pintype "passive"))
    )
    (net (code "46") (name "Net-(U5-CVDD)") (class "Default")
      (node (ref "C13") (pin "2") (pinfunction "2_2") (pintype "passive"))
      (node (ref "U5") (pin "3") (pinfunction "CVDD_3") (pintype "passive"))
    )
    (net (code "47") (name "Net-(U5-F_CLK)") (class "Default")
      (node (ref "U5") (pin "17") (pinfunction "F_CLK_17") (pintype "passive"))
      (node (ref "U5") (pin "22") (pinfunction "P16_22") (pintype "passive"))
    )
    (net (code "48") (name "Net-(U5-F_DI)") (class "Default")
      (node (ref "U5") (pin "18") (pinfunction "F_DI_18") (pintype "passive"))
      (node (ref "U5") (pin "20") (pinfunction "P14_20") (pintype "passive"))
    )
    (net (code "49") (name "Net-(U5-F_DO)") (class "Default")
      (node (ref "U5") (pin "14") (pinfunction "F_DO_14") (pintype "passive"))
      (node (ref "U5") (pin "19") (pinfunction "P13_19") (pintype "passive"))
    )
    (net (code "50") (name "Net-(U5-OSCI)") (class "Default")
      (node (ref "R10") (pin "1") (pinfunction "1_1") (pintype "passive"))
      (node (ref "U5") (pin "4") (pinfunction "OSCI_4") (pintype "passive"))
    )
    (net (code "51") (name "Net-(U5-P15)") (class "Default")
      (node (ref "U5") (pin "13") (pinfunction "/F_CS_13") (pintype "passive"))
      (node (ref "U5") (pin "21") (pinfunction "P15_21") (pintype "passive"))
    )
    (net (code "52") (name "Net-(U5-VDD)") (class "Default")
      (node (ref "C12") (pin "2") (pinfunction "2_2") (pintype "passive"))
      (node (ref "R7") (pin "2") (pinfunction "2_2") (pintype "passive"))
      (node (ref "U5") (pin "1") (pinfunction "VDD_1") (pintype "passive"))
    )
    (net (code "53") (name "Net-(U5-~{RESET})") (class "Default")
      (node (ref "C16") (pin "2") (pinfunction "2_2") (pintype "passive"))
      (node (ref "R11") (pin "1") (pinfunction "1_1") (pintype "passive"))
      (node (ref "U5") (pin "5") (pinfunction "~{RESET}_5") (pintype "passive"))
    )
    (net (code "54") (name "Net-(U6-FC1{slash}Vin+)") (class "Default")
      (node (ref "C15") (pin "2") (pinfunction "2_2") (pintype "passive"))
      (node (ref "U6") (pin "3") (pinfunction "FC1/Vin+_3") (pintype "passive"))
    )
    (net (code "55") (name "Net-(U6-FC2)") (class "Default")
      (node (ref "C14") (pin "1") (pinfunction "1_1") (pintype "passive"))
      (node (ref "U6") (pin "2") (pinfunction "FC2_2") (pintype "passive"))
    )
    (net (code "56") (name "Net-(U6-Vin-)") (class "Default")
      (node (ref "R14") (pin "2") (pinfunction "2_2") (pintype "passive"))
      (node (ref "R16") (pin "2") (pinfunction "2_2") (pintype "passive"))
      (node (ref "U6") (pin "4") (pinfunction "Vin-_4") (pintype "passive"))
    )
    (net (code "57") (name "Net-(U6-Vo1)") (class "Default")
      (node (ref "J2") (pin "1") (pinfunction "1_1") (pintype "passive"))
      (node (ref "R16") (pin "1") (pinfunction "1_1") (pintype "passive"))
      (node (ref "U6") (pin "5") (pinfunction "Vo1_5") (pintype "passive"))
    )
    (net (code "58") (name "Net-(U6-Vo2)") (class "Default")
      (node (ref "J2") (pin "2") (pinfunction "2_2") (pintype "passive"))
      (node (ref "U6") (pin "8") (pinfunction "Vo2_8") (pintype "passive"))
    )
    (net (code "59") (name "Net-(U12-nHOLD)") (class "Default")
      (node (ref "R19") (pin "1") (pinfunction "1_1") (pintype "passive"))
      (node (ref "U12") (pin "7") (pinfunction "nHOLD_7") (pintype "passive"))
    )
    (net (code "60") (name "RFR_VCC") (class "Default")
      (node (ref "3") (pin "1") (pinfunction "TP_1") (pintype "passive"))
      (node (ref "C11") (pin "1") (pinfunction "1_1") (pintype "passive"))
      (node (ref "C20") (pin "1") (pinfunction "1_1") (pintype "passive"))
      (node (ref "C21") (pin "1") (pinfunction "1_1") (pintype "passive"))
      (node (ref "C22") (pin "1") (pinfunction "1_1") (pintype "passive"))
      (node (ref "C23") (pin "2") (pinfunction "2_2") (pintype "passive"))
      (node (ref "C25") (pin "2") (pinfunction "2_2") (pintype "passive"))
      (node (ref "C28") (pin "1") (pinfunction "1_1") (pintype "passive"))
      (node (ref "C29") (pin "1") (pinfunction "1_1") (pintype "passive"))
      (node (ref "C30") (pin "1") (pinfunction "1_1") (pintype "passive"))
      (node (ref "C31") (pin "2") (pinfunction "2_2") (pintype "passive"))
      (node (ref "C32") (pin "2") (pinfunction "2_2") (pintype "passive"))
      (node (ref "C8") (pin "2") (pinfunction "2_2") (pintype "passive"))
      (node (ref "P3") (pin "1") (pinfunction "1_1") (pintype "passive"))
      (node (ref "P5") (pin "1") (pinfunction "1_1") (pintype "passive"))
      (node (ref "P6") (pin "1") (pinfunction "1_1") (pintype "passive"))
      (node (ref "R1") (pin "1") (pinfunction "1_1") (pintype "passive"))
      (node (ref "R12") (pin "2") (pinfunction "2_2") (pintype "passive"))
      (node (ref "R13") (pin "2") (pinfunction "2_2") (pintype "passive"))
      (node (ref "R19") (pin "2") (pinfunction "2_2") (pintype "passive"))
      (node (ref "R21") (pin "1") (pinfunction "1_1") (pintype "passive"))
      (node (ref "R22") (pin "1") (pinfunction "1_1") (pintype "passive"))
      (node (ref "R8") (pin "2") (pinfunction "2_2") (pintype "passive"))
      (node (ref "R9") (pin "2") (pinfunction "2_2") (pintype "passive"))
      (node (ref "U11") (pin "4") (pinfunction "VCC_4") (pintype "passive"))
      (node (ref "U12") (pin "8") (pinfunction "VCC_8") (pintype "passive"))
      (node (ref "U2") (pin "2") (pinfunction "Vo_2") (pintype "passive"))
      (node (ref "U2") (pin "4") (pinfunction "4_4") (pintype "passive"))
      (node (ref "U4") (pin "8") (pinfunction "VCC_8") (pintype "passive"))
      (node (ref "U5") (pin "10") (pinfunction "VCC_10") (pintype "passive"))
      (node (ref "U5") (pin "15") (pinfunction "~{WP}_15") (pintype "passive"))
      (node (ref "U5") (pin "23") (pinfunction "VDD_SIM_23") (pintype "passive"))
      (node (ref "U9") (pin "33") (pinfunction "VREFP_33") (pintype "passive"))
      (node (ref "U9") (pin "43") (pinfunction "VDDA_43") (pintype "passive"))
      (node (ref "U9") (pin "44") (pinfunction "VDD_44") (pintype "passive"))
      (node (ref "U9") (pin "8") (pinfunction "VDD_8") (pintype "passive"))
    )
    (net (code "61") (name "VCC5V") (class "Default")
      (node (ref "2") (pin "1") (pinfunction "TP_1") (pintype "passive"))
      (node (ref "C10") (pin "1") (pinfunction "1_1") (pintype "passive"))
      (node (ref "C3") (pin "1") (pinfunction "1_1") (pintype "passive"))
      (node (ref "C7") (pin "2") (pinfunction "2_2") (pintype "passive"))
      (node (ref "C9") (pin "1") (pinfunction "1_1") (pintype "passive"))
      (node (ref "D2") (pin "2") (pinfunction "K_2") (pintype "passive"))
      (node (ref "K1") (pin "5") (pinfunction "5_5") (pintype "passive"))
      (node (ref "L1") (pin "2") (pinfunction "2_2") (pintype "passive"))
      (node (ref "L2") (pin "2") (pinfunction "2_2") (pintype "passive"))
      (node (ref "P7") (pin "1") (pinfunction "1_1") (pintype "passive"))
      (node (ref "P7") (pin "2") (pinfunction "2_2") (pintype "passive"))
      (node (ref "R11") (pin "2") (pinfunction "2_2") (pintype "passive"))
      (node (ref "R2") (pin "2") (pinfunction "2_2") (pintype "passive"))
      (node (ref "R7") (pin "1") (pinfunction "1_1") (pintype "passive"))
      (node (ref "U2") (pin "3") (pinfunction "Vi_3") (pintype "passive"))
      (node (ref "U5") (pin "7") (pinfunction "VDD_SPK_7") (pintype "passive"))
      (node (ref "U6") (pin "6") (pinfunction "Vcc_6") (pintype "passive"))
    )
    (net (code "62") (name "VCC12V") (class "Default")
      (node (ref "1") (pin "1") (pinfunction "TP_1") (pintype "passive"))
      (node (ref "C4") (pin "1") (pinfunction "1_1") (pintype "passive"))
      (node (ref "C5") (pin "2") (pinfunction "2_2") (pintype "passive"))
      (node (ref "D1") (pin "2") (pinfunction "K_2") (pintype "passive"))
      (node (ref "U1") (pin "2") (pinfunction "IN_2") (pintype "passive"))
      (node (ref "U1") (pin "3") (pinfunction "EN_3") (pintype "passive"))
    )
    (net (code "63") (name "VCC_SIG") (class "Default")
      (node (ref "C2") (pin "1") (pinfunction "1_1") (pintype "passive"))
      (node (ref "L1") (pin "1") (pinfunction "1_1") (pintype "passive"))
      (node (ref "P4") (pin "1") (pinfunction "1_1") (pintype "passive"))
    )
    (net (code "64") (name "unconnected-(P7-Pad7)") (class "Default")
      (node (ref "P7") (pin "7") (pinfunction "7_7") (pintype "passive"))
    )
    (net (code "65") (name "unconnected-(P7-Pad8)") (class "Default")
      (node (ref "P7") (pin "8") (pinfunction "8_8") (pintype "passive"))
    )
    (net (code "66") (name "unconnected-(P7-Pad9)") (class "Default")
      (node (ref "P7") (pin "9") (pinfunction "9_9") (pintype "passive"))
    )
    (net (code "67") (name "unconnected-(U4-ADC-Pad2)") (class "Default")
      (node (ref "U4") (pin "2") (pinfunction "ADC_2") (pintype "passive+no_connect"))
    )
    (net (code "68") (name "unconnected-(U4-GPIO4-Pad19)") (class "Default")
      (node (ref "U4") (pin "19") (pinfunction "GPIO4_19") (pintype "passive+no_connect"))
    )
    (net (code "69") (name "unconnected-(U4-GPIO5-Pad20)") (class "Default")
      (node (ref "U4") (pin "20") (pinfunction "GPIO5_20") (pintype "passive+no_connect"))
    )
    (net (code "70") (name "unconnected-(U4-GPIO12-Pad6)") (class "Default")
      (node (ref "U4") (pin "6") (pinfunction "GPIO12_6") (pintype "passive+no_connect"))
    )
    (net (code "71") (name "unconnected-(U4-GPIO13-Pad7)") (class "Default")
      (node (ref "U4") (pin "7") (pinfunction "GPIO13_7") (pintype "passive+no_connect"))
    )
    (net (code "72") (name "unconnected-(U4-GPIO14-Pad5)") (class "Default")
      (node (ref "U4") (pin "5") (pinfunction "GPIO14_5") (pintype "passive+no_connect"))
    )
    (net (code "73") (name "unconnected-(U4-GPIO16-Pad4)") (class "Default")
      (node (ref "U4") (pin "4") (pinfunction "GPIO16_4") (pintype "passive+no_connect"))
    )
    (net (code "74") (name "unconnected-(U5-NC-Pad12)") (class "Default")
      (node (ref "U5") (pin "12") (pinfunction "NC_12") (pintype "passive"))
    )
    (net (code "75") (name "unconnected-(U5-P00-Pad24)") (class "Default")
      (node (ref "U5") (pin "24") (pinfunction "P00_24") (pintype "passive"))
    )
    (net (code "76") (name "unconnected-(U5-P01-Pad25)") (class "Default")
      (node (ref "U5") (pin "25") (pinfunction "P01_25") (pintype "passive"))
    )
    (net (code "77") (name "unconnected-(U5-P02-Pad26)") (class "Default")
      (node (ref "U5") (pin "26") (pinfunction "P02_26") (pintype "passive"))
    )
    (net (code "78") (name "unconnected-(U5-P04-Pad28)") (class "Default")
      (node (ref "U5") (pin "28") (pinfunction "P04_28") (pintype "passive"))
    )
    (net (code "79") (name "unconnected-(U5-PWM--Pad8)") (class "Default")
      (node (ref "U5") (pin "8") (pinfunction "PWM-_8") (pintype "passive"))
    )
    (net (code "80") (name "unconnected-(U9-P0_4-Pad15)") (class "Default")
      (node (ref "U9") (pin "15") (pinfunction "P0_4_15") (pintype "passive"))
    )
    (net (code "81") (name "unconnected-(U9-P0_5-Pad16)") (class "Default")
      (node (ref "U9") (pin "16") (pinfunction "P0_5_16") (pintype "passive"))
    )
    (net (code "82") (name "unconnected-(U9-P1_2-Pad35)") (class "Default")
      (node (ref "U9") (pin "35") (pinfunction "P1_2_35") (pintype "passive"))
    )
    (net (code "83") (name "unconnected-(U9-P1_9-Pad17)") (class "Default")
      (node (ref "U9") (pin "17") (pinfunction "P1_9_17") (pintype "passive"))
    )
    (net (code "84") (name "unconnected-(U9-P2_0-Pad2)") (class "Default")
      (node (ref "U9") (pin "2") (pinfunction "P2_0_2") (pintype "passive"))
    )
    (net (code "85") (name "unconnected-(U9-P2_3-Pad37)") (class "Default")
      (node (ref "U9") (pin "37") (pinfunction "P2_3_37") (pintype "passive"))
    )
    (net (code "86") (name "unconnected-(U9-P2_4-Pad19)") (class "Default")
      (node (ref "U9") (pin "19") (pinfunction "P2_4_19") (pintype "passive"))
    )
    (net (code "87") (name "unconnected-(U9-P2_6-Pad1)") (class "Default")
      (node (ref "U9") (pin "1") (pinfunction "P2_6_1") (pintype "passive"))
    )
    (net (code "88") (name "unconnected-(U9-P2_8-Pad12)") (class "Default")
      (node (ref "U9") (pin "12") (pinfunction "P2_8_12") (pintype "passive"))
    )
    (net (code "89") (name "unconnected-(U9-P2_9-Pad24)") (class "Default")
      (node (ref "U9") (pin "24") (pinfunction "P2_9_24") (pintype "passive"))
    )
    (net (code "90") (name "unconnected-(U9-P3_4-Pad18)") (class "Default")
      (node (ref "U9") (pin "18") (pinfunction "P3_4_18") (pintype "passive"))
    )
    (net (code "91") (name "unconnected-(U9-XTALIN-Pad6)") (class "Default")
      (node (ref "U9") (pin "6") (pinfunction "XTALIN_6") (pintype "passive"))
    )
    (net (code "92") (name "unconnected-(U9-XTALOUT-Pad7)") (class "Default")
      (node (ref "U9") (pin "7") (pinfunction "XTALOUT_7") (pintype "passive"))
    )
  )
)
